# RS485-CANBUS-WeMos.net
KiCad netlist of a schematic drawn in EAGLE
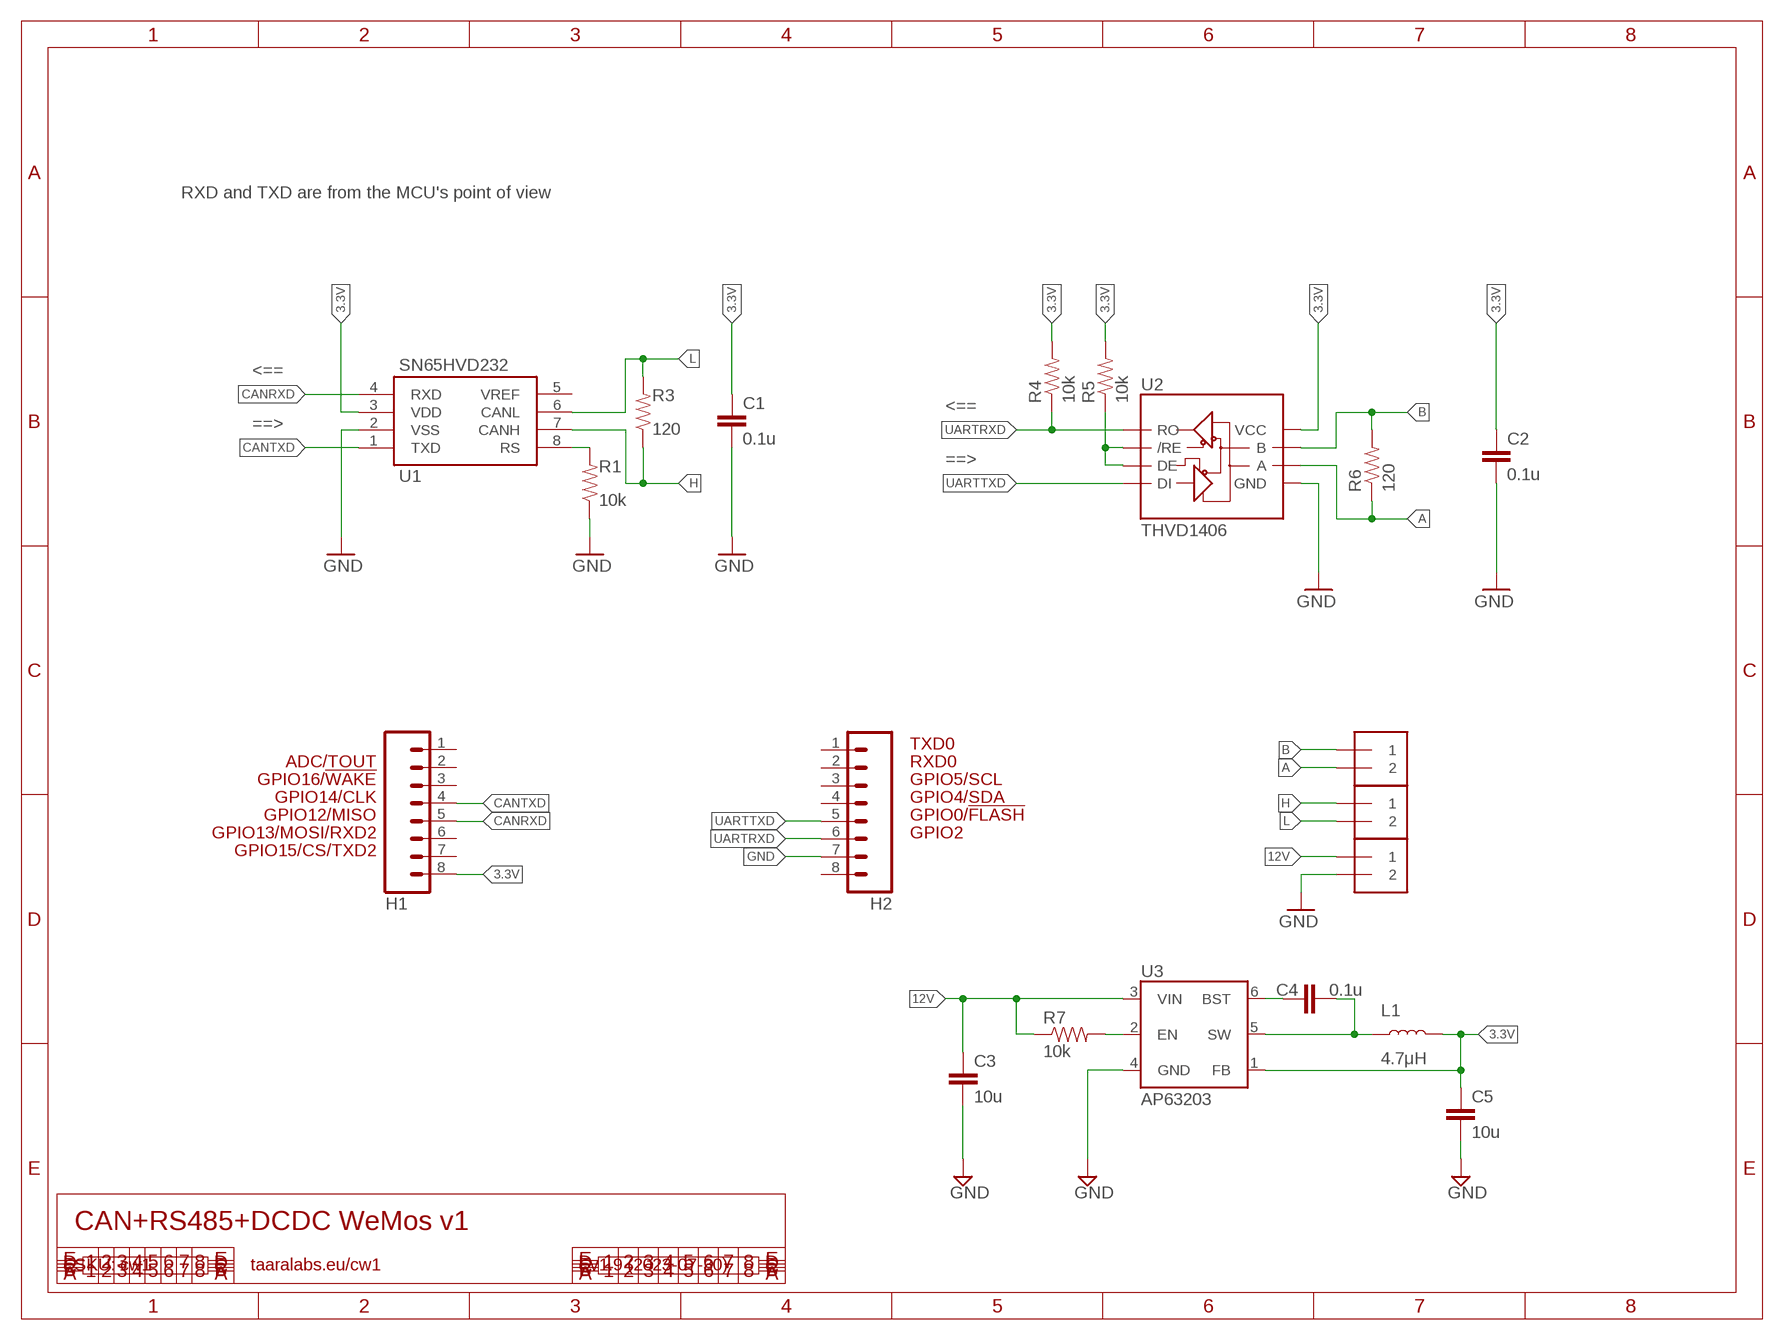
[diagram p0: schematic, sheet 1]

(export (version "E")
  (design (tool "Eeschema 10.0.6"))
  (components
    (comp (ref "C1")
      (value "0.1u")
      (footprint "eagle-import:0805")
      (libsource (lib "eagle-import") (part "CAP0805"))
    )
    (comp (ref "C2")
      (value "0.1u")
      (footprint "eagle-import:0805")
      (libsource (lib "eagle-import") (part "CAP0805"))
    )
    (comp (ref "C3")
      (value "10u")
      (footprint "eagle-import:1210")
      (libsource (lib "eagle-import") (part "CAP1210"))
    )
    (comp (ref "C4")
      (value "0.1u")
      (footprint "eagle-import:0805")
      (libsource (lib "eagle-import") (part "CAP0805"))
    )
    (comp (ref "C5")
      (value "10u")
      (footprint "eagle-import:0805")
      (libsource (lib "eagle-import") (part "CAP0805"))
    )
    (comp (ref "H1")
      (value "M08")
      (footprint "eagle-import:1X08")
      (libsource (lib "eagle-import") (part "M08"))
    )
    (comp (ref "H2")
      (value "M08")
      (footprint "eagle-import:1X08")
      (libsource (lib "eagle-import") (part "M08"))
    )
    (comp (ref "J1")
      (value "1X2-3.5MM")
      (footprint "eagle-import:1X2-3.5MM")
      (libsource (lib "eagle-import") (part "1X2-3.5MM"))
    )
    (comp (ref "J2")
      (value "1X2-3.5MM")
      (footprint "eagle-import:1X2-3.5MM")
      (libsource (lib "eagle-import") (part "1X2-3.5MM"))
    )
    (comp (ref "J3")
      (value "1X2-3.5MM")
      (footprint "eagle-import:1X2-3.5MM")
      (libsource (lib "eagle-import") (part "1X2-3.5MM"))
    )
    (comp (ref "L1")
      (value "4.7μH")
      (footprint "eagle-import:INDUCTOR_4X4MM")
      (libsource (lib "eagle-import") (part "4.7μH_SHIELDED_INDUCTORNPIS_LS"))
    )
    (comp (ref "R1")
      (value "10k")
      (footprint "eagle-import:0805")
      (libsource (lib "eagle-import") (part "RESISTOR0805-RES"))
    )
    (comp (ref "R3")
      (value "120")
      (footprint "eagle-import:0805")
      (libsource (lib "eagle-import") (part "RESISTOR0805-RES"))
    )
    (comp (ref "R4")
      (value "10k")
      (footprint "eagle-import:0805")
      (libsource (lib "eagle-import") (part "RESISTOR0805-RES"))
    )
    (comp (ref "R5")
      (value "10k")
      (footprint "eagle-import:0805")
      (libsource (lib "eagle-import") (part "RESISTOR0805-RES"))
    )
    (comp (ref "R6")
      (value "120")
      (footprint "eagle-import:0805")
      (libsource (lib "eagle-import") (part "RESISTOR0805-RES"))
    )
    (comp (ref "R7")
      (value "10k")
      (footprint "eagle-import:0805")
      (libsource (lib "eagle-import") (part "RESISTOR0805-RES"))
    )
    (comp (ref "U1")
      (value "SN65HVD232")
      (footprint "eagle-import:SO08")
      (libsource (lib "eagle-import") (part "MCP2551"))
    )
    (comp (ref "U2")
      (value "THVD1406")
      (footprint "eagle-import:SO08")
      (libsource (lib "eagle-import") (part "RS485SOIC"))
    )
    (comp (ref "U3")
      (value "AP63203")
      (footprint "eagle-import:SOT23-6")
      (libsource (lib "eagle-import") (part "AP63203"))
    )
  )
  (nets
    (net (code "1") (name "3.3V") (class "Default")
      (node (ref "C1") (pin "1") (pinfunction "1_1") (pintype "passive"))
      (node (ref "C2") (pin "1") (pinfunction "1_1") (pintype "passive"))
      (node (ref "C5") (pin "1") (pinfunction "1_1") (pintype "passive"))
      (node (ref "H1") (pin "8") (pinfunction "8_8") (pintype "passive"))
      (node (ref "L1") (pin "P$2") (pinfunction "2_P$2") (pintype "passive"))
      (node (ref "R4") (pin "2") (pinfunction "2_2") (pintype "passive"))
      (node (ref "R5") (pin "2") (pinfunction "2_2") (pintype "passive"))
      (node (ref "U1") (pin "3") (pinfunction "VDD_3") (pintype "bidirectional"))
      (node (ref "U2") (pin "8") (pinfunction "VCC_8") (pintype "bidirectional"))
      (node (ref "U3") (pin "1") (pinfunction "FB_1") (pintype "bidirectional"))
    )
    (net (code "2") (name "12V") (class "Default")
      (node (ref "C3") (pin "1") (pinfunction "1_1") (pintype "passive"))
      (node (ref "J2") (pin "1") (pinfunction "1_1") (pintype "passive"))
      (node (ref "R7") (pin "1") (pinfunction "1_1") (pintype "passive"))
      (node (ref "U3") (pin "3") (pinfunction "VIN_3") (pintype "bidirectional"))
    )
    (net (code "3") (name "A") (class "Default")
      (node (ref "J3") (pin "2") (pinfunction "2_2") (pintype "passive"))
      (node (ref "R6") (pin "1") (pinfunction "1_1") (pintype "passive"))
      (node (ref "U2") (pin "6") (pinfunction "A_6") (pintype "bidirectional"))
    )
    (net (code "4") (name "B") (class "Default")
      (node (ref "J3") (pin "1") (pinfunction "1_1") (pintype "passive"))
      (node (ref "R6") (pin "2") (pinfunction "2_2") (pintype "passive"))
      (node (ref "U2") (pin "7") (pinfunction "B_7") (pintype "bidirectional"))
    )
    (net (code "5") (name "CANRXD") (class "Default")
      (node (ref "H1") (pin "5") (pinfunction "5_5") (pintype "passive"))
      (node (ref "U1") (pin "4") (pinfunction "RXD_4") (pintype "bidirectional"))
    )
    (net (code "6") (name "CANTXD") (class "Default")
      (node (ref "H1") (pin "4") (pinfunction "4_4") (pintype "passive"))
      (node (ref "U1") (pin "1") (pinfunction "TXD_1") (pintype "bidirectional"))
    )
    (net (code "7") (name "GND") (class "Default")
      (node (ref "C1") (pin "2") (pinfunction "2_2") (pintype "passive"))
      (node (ref "C2") (pin "2") (pinfunction "2_2") (pintype "passive"))
      (node (ref "C3") (pin "2") (pinfunction "2_2") (pintype "passive"))
      (node (ref "C5") (pin "2") (pinfunction "2_2") (pintype "passive"))
      (node (ref "H2") (pin "7") (pinfunction "7_7") (pintype "passive"))
      (node (ref "J2") (pin "2") (pinfunction "2_2") (pintype "passive"))
      (node (ref "R1") (pin "1") (pinfunction "1_1") (pintype "passive"))
      (node (ref "U1") (pin "2") (pinfunction "VSS_2") (pintype "bidirectional"))
      (node (ref "U2") (pin "5") (pinfunction "GND_5") (pintype "bidirectional"))
      (node (ref "U3") (pin "4") (pinfunction "GND_4") (pintype "bidirectional"))
    )
    (net (code "8") (name "H") (class "Default")
      (node (ref "J1") (pin "1") (pinfunction "1_1") (pintype "passive"))
      (node (ref "R3") (pin "1") (pinfunction "1_1") (pintype "passive"))
      (node (ref "U1") (pin "7") (pinfunction "CANH_7") (pintype "bidirectional"))
    )
    (net (code "9") (name "L") (class "Default")
      (node (ref "J1") (pin "2") (pinfunction "2_2") (pintype "passive"))
      (node (ref "R3") (pin "2") (pinfunction "2_2") (pintype "passive"))
      (node (ref "U1") (pin "6") (pinfunction "CANL_6") (pintype "bidirectional"))
    )
    (net (code "10") (name "Net-(L1-1)") (class "Default")
      (node (ref "C4") (pin "2") (pinfunction "2_2") (pintype "passive"))
      (node (ref "L1") (pin "P$1") (pinfunction "1_P$1") (pintype "passive"))
      (node (ref "U3") (pin "5") (pinfunction "SW_5") (pintype "bidirectional"))
    )
    (net (code "11") (name "Net-(U1-RS)") (class "Default")
      (node (ref "R1") (pin "2") (pinfunction "2_2") (pintype "passive"))
      (node (ref "U1") (pin "8") (pinfunction "RS_8") (pintype "bidirectional"))
    )
    (net (code "12") (name "Net-(U2-DE)") (class "Default")
      (node (ref "R5") (pin "1") (pinfunction "1_1") (pintype "passive"))
      (node (ref "U2") (pin "2") (pinfunction "/RE_2") (pintype "bidirectional"))
      (node (ref "U2") (pin "3") (pinfunction "DE_3") (pintype "bidirectional"))
    )
    (net (code "13") (name "Net-(U3-BST)") (class "Default")
      (node (ref "C4") (pin "1") (pinfunction "1_1") (pintype "passive"))
      (node (ref "U3") (pin "6") (pinfunction "BST_6") (pintype "bidirectional"))
    )
    (net (code "14") (name "Net-(U3-EN)") (class "Default")
      (node (ref "R7") (pin "2") (pinfunction "2_2") (pintype "passive"))
      (node (ref "U3") (pin "2") (pinfunction "EN_2") (pintype "bidirectional"))
    )
    (net (code "15") (name "UARTRXD") (class "Default")
      (node (ref "H2") (pin "6") (pinfunction "6_6") (pintype "passive"))
      (node (ref "R4") (pin "1") (pinfunction "1_1") (pintype "passive"))
      (node (ref "U2") (pin "1") (pinfunction "RO_1") (pintype "bidirectional"))
    )
    (net (code "16") (name "UARTTXD") (class "Default")
      (node (ref "H2") (pin "5") (pinfunction "5_5") (pintype "passive"))
      (node (ref "U2") (pin "4") (pinfunction "DI_4") (pintype "bidirectional"))
    )
    (net (code "17") (name "unconnected-(H1-Pad1)") (class "Default")
      (node (ref "H1") (pin "1") (pinfunction "1_1") (pintype "passive"))
    )
    (net (code "18") (name "unconnected-(H1-Pad2)") (class "Default")
      (node (ref "H1") (pin "2") (pinfunction "2_2") (pintype "passive"))
    )
    (net (code "19") (name "unconnected-(H1-Pad3)") (class "Default")
      (node (ref "H1") (pin "3") (pinfunction "3_3") (pintype "passive"))
    )
    (net (code "20") (name "unconnected-(H1-Pad6)") (class "Default")
      (node (ref "H1") (pin "6") (pinfunction "6_6") (pintype "passive"))
    )
    (net (code "21") (name "unconnected-(H1-Pad7)") (class "Default")
      (node (ref "H1") (pin "7") (pinfunction "7_7") (pintype "passive"))
    )
    (net (code "22") (name "unconnected-(H2-Pad1)") (class "Default")
      (node (ref "H2") (pin "1") (pinfunction "1_1") (pintype "passive"))
    )
    (net (code "23") (name "unconnected-(H2-Pad2)") (class "Default")
      (node (ref "H2") (pin "2") (pinfunction "2_2") (pintype "passive"))
    )
    (net (code "24") (name "unconnected-(H2-Pad3)") (class "Default")
      (node (ref "H2") (pin "3") (pinfunction "3_3") (pintype "passive"))
    )
    (net (code "25") (name "unconnected-(H2-Pad4)") (class "Default")
      (node (ref "H2") (pin "4") (pinfunction "4_4") (pintype "passive"))
    )
    (net (code "26") (name "unconnected-(H2-Pad8)") (class "Default")
      (node (ref "H2") (pin "8") (pinfunction "8_8") (pintype "passive"))
    )
    (net (code "27") (name "unconnected-(U1-VREF-Pad5)") (class "Default")
      (node (ref "U1") (pin "5") (pinfunction "VREF_5") (pintype "bidirectional"))
    )
  )
)
